# bike_sensor.net
KiCad netlist of a schematic drawn in EAGLE
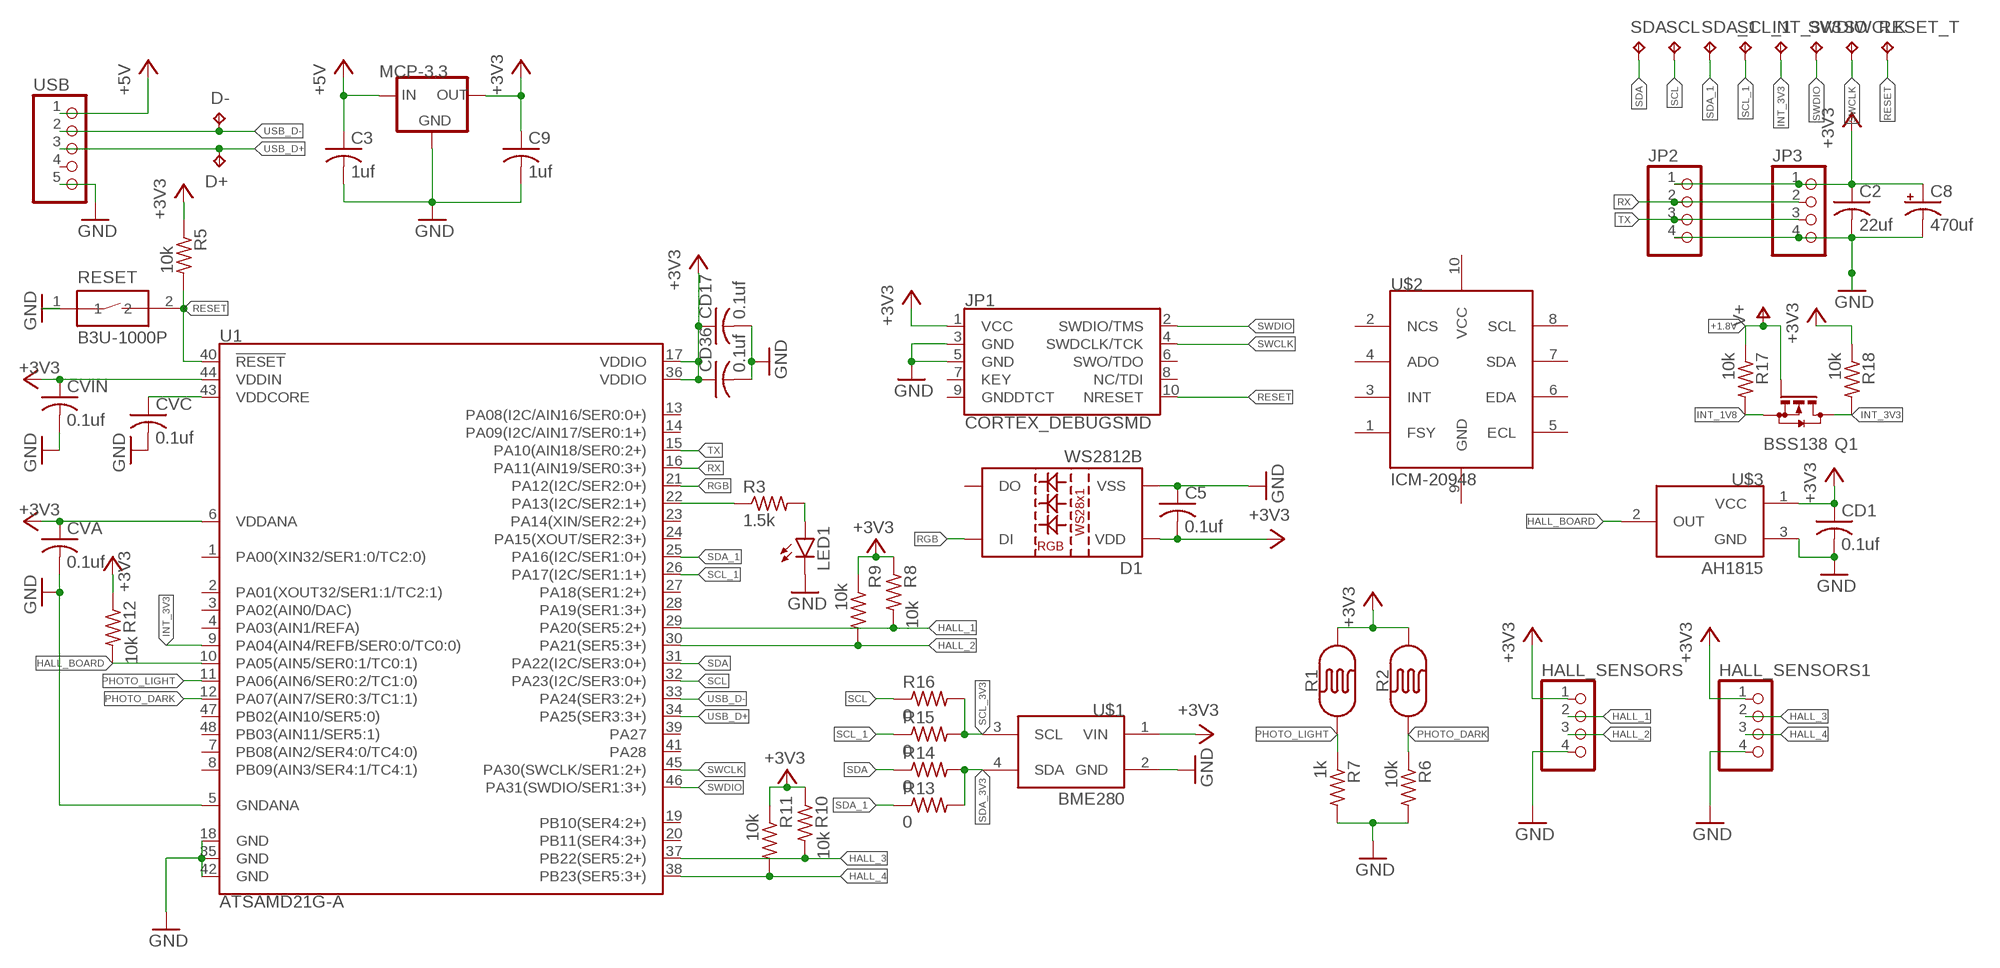
[diagram p0: schematic, sheet 1]

(export (version "E")
  (design (tool "Eeschema 10.0.6"))
  (components
    (comp (ref "C2")
      (value "22uf")
      (footprint "eagle-import:C1210")
      (libsource (lib "eagle-import") (part "C-USC1210"))
    )
    (comp (ref "C3")
      (value "1uf")
      (footprint "eagle-import:C1210")
      (libsource (lib "eagle-import") (part "C-USC1210"))
    )
    (comp (ref "C5")
      (value "0.1uf")
      (footprint "eagle-import:C0805")
      (libsource (lib "eagle-import") (part "C-USC0805"))
    )
    (comp (ref "C8")
      (value "470uf")
      (footprint "eagle-import:UD-8X10_NICHICON")
      (libsource (lib "eagle-import") (part "CPOL-USUD-8X10"))
    )
    (comp (ref "C9")
      (value "1uf")
      (footprint "eagle-import:C1210")
      (libsource (lib "eagle-import") (part "C-USC1210"))
    )
    (comp (ref "CD1")
      (value "0.1uf")
      (footprint "eagle-import:C0805")
      (libsource (lib "eagle-import") (part "C-USC0805"))
    )
    (comp (ref "CD17")
      (value "0.1uf")
      (footprint "eagle-import:C0805")
      (libsource (lib "eagle-import") (part "C-USC0805"))
    )
    (comp (ref "CD36")
      (value "0.1uf")
      (footprint "eagle-import:C0805")
      (libsource (lib "eagle-import") (part "C-USC0805"))
    )
    (comp (ref "CVA")
      (value "0.1uf")
      (footprint "eagle-import:C0805")
      (libsource (lib "eagle-import") (part "C-USC0805"))
    )
    (comp (ref "CVC")
      (value "0.1uf")
      (footprint "eagle-import:C0805")
      (libsource (lib "eagle-import") (part "C-USC0805"))
    )
    (comp (ref "CVIN")
      (value "0.1uf")
      (footprint "eagle-import:C0805")
      (libsource (lib "eagle-import") (part "C-USC0805"))
    )
    (comp (ref "D+")
      (value "TPB1,27")
      (footprint "eagle-import:B1,27")
      (libsource (lib "eagle-import") (part "TPB1,27"))
    )
    (comp (ref "D-")
      (value "TPB1,27")
      (footprint "eagle-import:B1,27")
      (libsource (lib "eagle-import") (part "TPB1,27"))
    )
    (comp (ref "D1")
      (value "WS2812B")
      (footprint "eagle-import:WS2812B")
      (libsource (lib "eagle-import") (part "WS2812B"))
    )
    (comp (ref "HALL_SENSORS")
      (value "PINHD-1X4")
      (footprint "eagle-import:1X04")
      (libsource (lib "eagle-import") (part "PINHD-1X4"))
    )
    (comp (ref "HALL_SENSORS1")
      (value "PINHD-1X4")
      (footprint "eagle-import:1X04")
      (libsource (lib "eagle-import") (part "PINHD-1X4"))
    )
    (comp (ref "INT_3V3")
      (value "TPB1,27")
      (footprint "eagle-import:B1,27")
      (libsource (lib "eagle-import") (part "TPB1,27"))
    )
    (comp (ref "JP1")
      (value "CORTEX_DEBUGSMD")
      (footprint "eagle-import:SAMTECH_FTSH-105-01")
      (libsource (lib "eagle-import") (part "CORTEX_DEBUGSMD"))
    )
    (comp (ref "JP2")
      (value "PINHD-1X4")
      (footprint "eagle-import:1X04")
      (libsource (lib "eagle-import") (part "PINHD-1X4"))
    )
    (comp (ref "JP3")
      (value "PINHD-1X4")
      (footprint "eagle-import:1X04")
      (libsource (lib "eagle-import") (part "PINHD-1X4"))
    )
    (comp (ref "LED1")
      (value "LEDCHIPLED_0805")
      (footprint "eagle-import:CHIPLED_0805")
      (libsource (lib "eagle-import") (part "LEDCHIPLED_0805"))
    )
    (comp (ref "MCP-3.3")
      (value "XC63FPM")
      (footprint "eagle-import:SOT23")
      (libsource (lib "eagle-import") (part "XC63FPM"))
    )
    (comp (ref "Q1")
      (value "BSS138")
      (footprint "eagle-import:SOT23")
      (libsource (lib "eagle-import") (part "BSS123"))
    )
    (comp (ref "R1")
      (value "PHOTOCELLPTH")
      (footprint "eagle-import:PHOTOCELL")
      (libsource (lib "eagle-import") (part "PHOTOCELLPTH"))
    )
    (comp (ref "R2")
      (value "PHOTOCELLPTH")
      (footprint "eagle-import:PHOTOCELL")
      (libsource (lib "eagle-import") (part "PHOTOCELLPTH"))
    )
    (comp (ref "R3")
      (value "1.5k")
      (footprint "eagle-import:R0805")
      (libsource (lib "eagle-import") (part "R-US_R0805"))
    )
    (comp (ref "R5")
      (value "10k")
      (footprint "eagle-import:R0805")
      (libsource (lib "eagle-import") (part "R-US_R0805"))
    )
    (comp (ref "R6")
      (value "10k")
      (footprint "eagle-import:R0805")
      (libsource (lib "eagle-import") (part "R-US_R0805"))
    )
    (comp (ref "R7")
      (value "1k")
      (footprint "eagle-import:R0805")
      (libsource (lib "eagle-import") (part "R-US_R0805"))
    )
    (comp (ref "R8")
      (value "10k")
      (footprint "eagle-import:R0805")
      (libsource (lib "eagle-import") (part "R-US_R0805"))
    )
    (comp (ref "R9")
      (value "10k")
      (footprint "eagle-import:R0805")
      (libsource (lib "eagle-import") (part "R-US_R0805"))
    )
    (comp (ref "R10")
      (value "10k")
      (footprint "eagle-import:R0805")
      (libsource (lib "eagle-import") (part "R-US_R0805"))
    )
    (comp (ref "R11")
      (value "10k")
      (footprint "eagle-import:R0805")
      (libsource (lib "eagle-import") (part "R-US_R0805"))
    )
    (comp (ref "R12")
      (value "10k")
      (footprint "eagle-import:R0805")
      (libsource (lib "eagle-import") (part "R-US_R0805"))
    )
    (comp (ref "R13")
      (value "0")
      (footprint "eagle-import:R0603")
      (libsource (lib "eagle-import") (part "R-US_R0603"))
    )
    (comp (ref "R14")
      (value "0")
      (footprint "eagle-import:R0603")
      (libsource (lib "eagle-import") (part "R-US_R0603"))
    )
    (comp (ref "R15")
      (value "0")
      (footprint "eagle-import:R0603")
      (libsource (lib "eagle-import") (part "R-US_R0603"))
    )
    (comp (ref "R16")
      (value "0")
      (footprint "eagle-import:R0603")
      (libsource (lib "eagle-import") (part "R-US_R0603"))
    )
    (comp (ref "R17")
      (value "10k")
      (footprint "eagle-import:R0805")
      (libsource (lib "eagle-import") (part "R-US_R0805"))
    )
    (comp (ref "R18")
      (value "10k")
      (footprint "eagle-import:R0805")
      (libsource (lib "eagle-import") (part "R-US_R0805"))
    )
    (comp (ref "RESET")
      (value "B3U-1000P")
      (footprint "eagle-import:B3U-1000P")
      (fields
        (field (name "DIGI_KEY_PART_NUMBER") "SW1020CT-ND")
        (field (name "MANUFACTURER") "Omron Electronics Inc-EMC Div")
        (field (name "CREATED_BY") "PCBLayout.com")
      )
      (libsource (lib "eagle-import") (part "B3U-1000P"))
    )
    (comp (ref "RESET_T")
      (value "TPB1,27")
      (footprint "eagle-import:B1,27")
      (libsource (lib "eagle-import") (part "TPB1,27"))
    )
    (comp (ref "SCL")
      (value "TPB1,27")
      (footprint "eagle-import:B1,27")
      (libsource (lib "eagle-import") (part "TPB1,27"))
    )
    (comp (ref "SCL_1")
      (value "TPB1,27")
      (footprint "eagle-import:B1,27")
      (libsource (lib "eagle-import") (part "TPB1,27"))
    )
    (comp (ref "SDA")
      (value "TPB1,27")
      (footprint "eagle-import:B1,27")
      (libsource (lib "eagle-import") (part "TPB1,27"))
    )
    (comp (ref "SDA_1")
      (value "TPB1,27")
      (footprint "eagle-import:B1,27")
      (libsource (lib "eagle-import") (part "TPB1,27"))
    )
    (comp (ref "SWCLK")
      (value "TPB1,27")
      (footprint "eagle-import:B1,27")
      (libsource (lib "eagle-import") (part "TPB1,27"))
    )
    (comp (ref "SWDIO")
      (value "TPB1,27")
      (footprint "eagle-import:B1,27")
      (libsource (lib "eagle-import") (part "TPB1,27"))
    )
    (comp (ref "U$1")
      (value "BMP280")
      (footprint "eagle-import:BME280-BOARD")
      (libsource (lib "eagle-import") (part "BMP280"))
    )
    (comp (ref "U$2")
      (value "MPU9250")
      (footprint "eagle-import:ICM-20948-BOARD")
      (libsource (lib "eagle-import") (part "MPU9250"))
    )
    (comp (ref "U$3")
      (value "AH1815")
      (footprint "eagle-import:SOT23")
      (libsource (lib "eagle-import") (part "AH1815"))
    )
    (comp (ref "U1")
      (value "ATSAMD21G-A")
      (footprint "eagle-import:TQFP-48")
      (libsource (lib "eagle-import") (part "ATSAMD21G-A"))
    )
    (comp (ref "USB")
      (value "PINHD-1X5")
      (footprint "eagle-import:1X05")
      (libsource (lib "eagle-import") (part "PINHD-1X5"))
    )
  )
  (nets
    (net (code "1") (name "+1.8V") (class "Default")
      (node (ref "Q1") (pin "1") (pinfunction "G_1") (pintype "passive"))
      (node (ref "R17") (pin "1") (pinfunction "1_1") (pintype "passive"))
    )
    (net (code "2") (name "+3V3") (class "Default")
      (node (ref "C2") (pin "1") (pinfunction "1_1") (pintype "passive"))
      (node (ref "C5") (pin "2") (pinfunction "2_2") (pintype "passive"))
      (node (ref "C8") (pin "+") (pinfunction "+_+") (pintype "passive"))
      (node (ref "C9") (pin "1") (pinfunction "1_1") (pintype "passive"))
      (node (ref "CD1") (pin "1") (pinfunction "1_1") (pintype "passive"))
      (node (ref "CD17") (pin "1") (pinfunction "1_1") (pintype "passive"))
      (node (ref "CD36") (pin "1") (pinfunction "1_1") (pintype "passive"))
      (node (ref "CVA") (pin "1") (pinfunction "1_1") (pintype "passive"))
      (node (ref "CVIN") (pin "1") (pinfunction "1_1") (pintype "passive"))
      (node (ref "D1") (pin "1") (pinfunction "VDD_1") (pintype "bidirectional"))
      (node (ref "HALL_SENSORS") (pin "1") (pinfunction "1_1") (pintype "passive"))
      (node (ref "HALL_SENSORS1") (pin "1") (pinfunction "1_1") (pintype "passive"))
      (node (ref "JP1") (pin "1") (pinfunction "VCC_1") (pintype "bidirectional"))
      (node (ref "JP2") (pin "1") (pinfunction "1_1") (pintype "passive"))
      (node (ref "JP3") (pin "1") (pinfunction "1_1") (pintype "passive"))
      (node (ref "MCP-3.3") (pin "2") (pinfunction "OUT_2") (pintype "passive"))
      (node (ref "R1") (pin "2") (pinfunction "P$2_2") (pintype "bidirectional"))
      (node (ref "R10") (pin "1") (pinfunction "1_1") (pintype "passive"))
      (node (ref "R11") (pin "1") (pinfunction "1_1") (pintype "passive"))
      (node (ref "R12") (pin "1") (pinfunction "1_1") (pintype "passive"))
      (node (ref "R18") (pin "1") (pinfunction "1_1") (pintype "passive"))
      (node (ref "R2") (pin "2") (pinfunction "P$2_2") (pintype "bidirectional"))
      (node (ref "R5") (pin "1") (pinfunction "1_1") (pintype "passive"))
      (node (ref "R8") (pin "1") (pinfunction "1_1") (pintype "passive"))
      (node (ref "R9") (pin "1") (pinfunction "1_1") (pintype "passive"))
      (node (ref "U$1") (pin "1") (pinfunction "VIN_1") (pintype "bidirectional"))
      (node (ref "U$3") (pin "1") (pinfunction "VCC_1") (pintype "power_in"))
      (node (ref "U1") (pin "17") (pinfunction "VDDIO_17") (pintype "bidirectional"))
      (node (ref "U1") (pin "36") (pinfunction "VDDIO_36") (pintype "bidirectional"))
      (node (ref "U1") (pin "44") (pinfunction "VDDIN_44") (pintype "bidirectional"))
      (node (ref "U1") (pin "6") (pinfunction "VDDANA_6") (pintype "bidirectional"))
    )
    (net (code "3") (name "+5V") (class "Default")
      (node (ref "C3") (pin "1") (pinfunction "1_1") (pintype "passive"))
      (node (ref "MCP-3.3") (pin "3") (pinfunction "IN_3") (pintype "input"))
      (node (ref "USB") (pin "1") (pinfunction "1_1") (pintype "passive"))
    )
    (net (code "4") (name "/VCC") (class "Default")
      (node (ref "U$2") (pin "10") (pinfunction "VCC_10") (pintype "power_in"))
    )
    (net (code "5") (name "GND") (class "Default")
      (node (ref "C2") (pin "2") (pinfunction "2_2") (pintype "passive"))
      (node (ref "C3") (pin "2") (pinfunction "2_2") (pintype "passive"))
      (node (ref "C5") (pin "1") (pinfunction "1_1") (pintype "passive"))
      (node (ref "C8") (pin "-") (pinfunction "-_-") (pintype "passive"))
      (node (ref "C9") (pin "2") (pinfunction "2_2") (pintype "passive"))
      (node (ref "CD1") (pin "2") (pinfunction "2_2") (pintype "passive"))
      (node (ref "CD17") (pin "2") (pinfunction "2_2") (pintype "passive"))
      (node (ref "CD36") (pin "2") (pinfunction "2_2") (pintype "passive"))
      (node (ref "CVA") (pin "2") (pinfunction "2_2") (pintype "passive"))
      (node (ref "CVC") (pin "2") (pinfunction "2_2") (pintype "passive"))
      (node (ref "CVIN") (pin "2") (pinfunction "2_2") (pintype "passive"))
      (node (ref "D1") (pin "3") (pinfunction "VSS_3") (pintype "bidirectional"))
      (node (ref "HALL_SENSORS") (pin "4") (pinfunction "4_4") (pintype "passive"))
      (node (ref "HALL_SENSORS1") (pin "4") (pinfunction "4_4") (pintype "passive"))
      (node (ref "JP1") (pin "3") (pinfunction "GND_3") (pintype "bidirectional"))
      (node (ref "JP1") (pin "5") (pinfunction "GND_5") (pintype "bidirectional"))
      (node (ref "JP2") (pin "4") (pinfunction "4_4") (pintype "passive"))
      (node (ref "JP3") (pin "4") (pinfunction "4_4") (pintype "passive"))
      (node (ref "LED1") (pin "C") (pinfunction "C_C") (pintype "passive"))
      (node (ref "MCP-3.3") (pin "1") (pinfunction "GND_1") (pintype "input"))
      (node (ref "R6") (pin "2") (pinfunction "2_2") (pintype "passive"))
      (node (ref "R7") (pin "2") (pinfunction "2_2") (pintype "passive"))
      (node (ref "RESET") (pin "1") (pinfunction "1_1") (pintype "passive"))
      (node (ref "U$1") (pin "2") (pinfunction "GND_2") (pintype "bidirectional"))
      (node (ref "U$3") (pin "3") (pinfunction "GND_3") (pintype "power_in"))
      (node (ref "U1") (pin "18") (pinfunction "GND_18") (pintype "bidirectional"))
      (node (ref "U1") (pin "35") (pinfunction "GND_35") (pintype "bidirectional"))
      (node (ref "U1") (pin "42") (pinfunction "GND_42") (pintype "bidirectional"))
      (node (ref "U1") (pin "5") (pinfunction "GNDANA_5") (pintype "bidirectional"))
      (node (ref "USB") (pin "5") (pinfunction "5_5") (pintype "passive"))
    )
    (net (code "6") (name "HALL_1") (class "Default")
      (node (ref "HALL_SENSORS") (pin "2") (pinfunction "2_2") (pintype "passive"))
      (node (ref "R8") (pin "2") (pinfunction "2_2") (pintype "passive"))
      (node (ref "U1") (pin "29") (pinfunction "PA20(SER5:2+)_29") (pintype "bidirectional"))
    )
    (net (code "7") (name "HALL_2") (class "Default")
      (node (ref "HALL_SENSORS") (pin "3") (pinfunction "3_3") (pintype "passive"))
      (node (ref "R9") (pin "2") (pinfunction "2_2") (pintype "passive"))
      (node (ref "U1") (pin "30") (pinfunction "PA21(SER5:3+)_30") (pintype "bidirectional"))
    )
    (net (code "8") (name "HALL_3") (class "Default")
      (node (ref "HALL_SENSORS1") (pin "2") (pinfunction "2_2") (pintype "passive"))
      (node (ref "R10") (pin "2") (pinfunction "2_2") (pintype "passive"))
      (node (ref "U1") (pin "37") (pinfunction "PB22(SER5:2+)_37") (pintype "bidirectional"))
    )
    (net (code "9") (name "HALL_4") (class "Default")
      (node (ref "HALL_SENSORS1") (pin "3") (pinfunction "3_3") (pintype "passive"))
      (node (ref "R11") (pin "2") (pinfunction "2_2") (pintype "passive"))
      (node (ref "U1") (pin "38") (pinfunction "PB23(SER5:3+)_38") (pintype "bidirectional"))
    )
    (net (code "10") (name "HALL_BOARD") (class "Default")
      (node (ref "R12") (pin "2") (pinfunction "2_2") (pintype "passive"))
      (node (ref "U$3") (pin "2") (pinfunction "OUT_2") (pintype "output"))
      (node (ref "U1") (pin "10") (pinfunction "PA05(AIN5/SER0:1/TC0:1)_10") (pintype "bidirectional"))
    )
    (net (code "11") (name "INT_1V8") (class "Default")
      (node (ref "Q1") (pin "2") (pinfunction "S_2") (pintype "passive"))
      (node (ref "R17") (pin "2") (pinfunction "2_2") (pintype "passive"))
    )
    (net (code "12") (name "INT_3V3") (class "Default")
      (node (ref "INT_3V3") (pin "TP") (pinfunction "TP_TP") (pintype "input"))
      (node (ref "Q1") (pin "3") (pinfunction "D_3") (pintype "passive"))
      (node (ref "R18") (pin "2") (pinfunction "2_2") (pintype "passive"))
      (node (ref "U1") (pin "9") (pinfunction "PA04(AIN4/REFB/SER0:0/TC0:0)_9") (pintype "bidirectional"))
    )
    (net (code "13") (name "Net-(LED1-PadA)") (class "Default")
      (node (ref "LED1") (pin "A") (pinfunction "A_A") (pintype "passive"))
      (node (ref "R3") (pin "2") (pinfunction "2_2") (pintype "passive"))
    )
    (net (code "14") (name "Net-(U1-PA13(I2C{slash}SER2:1+))") (class "Default")
      (node (ref "R3") (pin "1") (pinfunction "1_1") (pintype "passive"))
      (node (ref "U1") (pin "22") (pinfunction "PA13(I2C/SER2:1+)_22") (pintype "bidirectional"))
    )
    (net (code "15") (name "Net-(U1-VDDCORE)") (class "Default")
      (node (ref "CVC") (pin "1") (pinfunction "1_1") (pintype "passive"))
      (node (ref "U1") (pin "43") (pinfunction "VDDCORE_43") (pintype "bidirectional"))
    )
    (net (code "16") (name "PHOTO_DARK") (class "Default")
      (node (ref "R2") (pin "1") (pinfunction "P$1_1") (pintype "bidirectional"))
      (node (ref "R6") (pin "1") (pinfunction "1_1") (pintype "passive"))
      (node (ref "U1") (pin "12") (pinfunction "PA07(AIN7/SER0:3/TC1:1)_12") (pintype "bidirectional"))
    )
    (net (code "17") (name "PHOTO_LIGHT") (class "Default")
      (node (ref "R1") (pin "1") (pinfunction "P$1_1") (pintype "bidirectional"))
      (node (ref "R7") (pin "1") (pinfunction "1_1") (pintype "passive"))
      (node (ref "U1") (pin "11") (pinfunction "PA06(AIN6/SER0:2/TC1:0)_11") (pintype "bidirectional"))
    )
    (net (code "18") (name "RESET") (class "Default")
      (node (ref "JP1") (pin "10") (pinfunction "NRESET_10") (pintype "bidirectional"))
      (node (ref "R5") (pin "2") (pinfunction "2_2") (pintype "passive"))
      (node (ref "RESET") (pin "2") (pinfunction "2_2") (pintype "passive"))
      (node (ref "RESET_T") (pin "TP") (pinfunction "TP_TP") (pintype "input"))
      (node (ref "U1") (pin "40") (pinfunction "~{RESET}_40") (pintype "bidirectional"))
    )
    (net (code "19") (name "RGB") (class "Default")
      (node (ref "D1") (pin "4") (pinfunction "DI_4") (pintype "bidirectional"))
      (node (ref "U1") (pin "21") (pinfunction "PA12(I2C/SER2:0+)_21") (pintype "bidirectional"))
    )
    (net (code "20") (name "RX") (class "Default")
      (node (ref "JP2") (pin "2") (pinfunction "2_2") (pintype "passive"))
      (node (ref "JP3") (pin "2") (pinfunction "2_2") (pintype "passive"))
      (node (ref "U1") (pin "16") (pinfunction "PA11(AIN19/SER0:3+)_16") (pintype "bidirectional"))
    )
    (net (code "21") (name "SCL") (class "Default")
      (node (ref "R16") (pin "1") (pinfunction "1_1") (pintype "passive"))
      (node (ref "SCL") (pin "TP") (pinfunction "TP_TP") (pintype "input"))
      (node (ref "U1") (pin "32") (pinfunction "PA23(I2C/SER3:0+)_32") (pintype "bidirectional"))
    )
    (net (code "22") (name "SCL_1") (class "Default")
      (node (ref "R15") (pin "1") (pinfunction "1_1") (pintype "passive"))
      (node (ref "SCL_1") (pin "TP") (pinfunction "TP_TP") (pintype "input"))
      (node (ref "U1") (pin "26") (pinfunction "PA17(I2C/SER1:1+)_26") (pintype "bidirectional"))
    )
    (net (code "23") (name "SCL_3V3") (class "Default")
      (node (ref "R15") (pin "2") (pinfunction "2_2") (pintype "passive"))
      (node (ref "R16") (pin "2") (pinfunction "2_2") (pintype "passive"))
      (node (ref "U$1") (pin "3") (pinfunction "SCL_3") (pintype "bidirectional"))
    )
    (net (code "24") (name "SDA") (class "Default")
      (node (ref "R14") (pin "1") (pinfunction "1_1") (pintype "passive"))
      (node (ref "SDA") (pin "TP") (pinfunction "TP_TP") (pintype "input"))
      (node (ref "U1") (pin "31") (pinfunction "PA22(I2C/SER3:0+)_31") (pintype "bidirectional"))
    )
    (net (code "25") (name "SDA_1") (class "Default")
      (node (ref "R13") (pin "1") (pinfunction "1_1") (pintype "passive"))
      (node (ref "SDA_1") (pin "TP") (pinfunction "TP_TP") (pintype "input"))
      (node (ref "U1") (pin "25") (pinfunction "PA16(I2C/SER1:0+)_25") (pintype "bidirectional"))
    )
    (net (code "26") (name "SDA_3V3") (class "Default")
      (node (ref "R13") (pin "2") (pinfunction "2_2") (pintype "passive"))
      (node (ref "R14") (pin "2") (pinfunction "2_2") (pintype "passive"))
      (node (ref "U$1") (pin "4") (pinfunction "SDA_4") (pintype "bidirectional"))
    )
    (net (code "27") (name "SWCLK") (class "Default")
      (node (ref "JP1") (pin "4") (pinfunction "SWDCLK/TCK_4") (pintype "bidirectional"))
      (node (ref "SWCLK") (pin "TP") (pinfunction "TP_TP") (pintype "input"))
      (node (ref "U1") (pin "45") (pinfunction "PA30(SWCLK/SER1:2+)_45") (pintype "bidirectional"))
    )
    (net (code "28") (name "SWDIO") (class "Default")
      (node (ref "JP1") (pin "2") (pinfunction "SWDIO/TMS_2") (pintype "bidirectional"))
      (node (ref "SWDIO") (pin "TP") (pinfunction "TP_TP") (pintype "input"))
      (node (ref "U1") (pin "46") (pinfunction "PA31(SWDIO/SER1:3+)_46") (pintype "bidirectional"))
    )
    (net (code "29") (name "TX") (class "Default")
      (node (ref "JP2") (pin "3") (pinfunction "3_3") (pintype "passive"))
      (node (ref "JP3") (pin "3") (pinfunction "3_3") (pintype "passive"))
      (node (ref "U1") (pin "15") (pinfunction "PA10(AIN18/SER0:2+)_15") (pintype "bidirectional"))
    )
    (net (code "30") (name "USB_D+") (class "Default")
      (node (ref "D+") (pin "TP") (pinfunction "TP_TP") (pintype "input"))
      (node (ref "U1") (pin "34") (pinfunction "PA25(SER3:3+)_34") (pintype "bidirectional"))
      (node (ref "USB") (pin "3") (pinfunction "3_3") (pintype "passive"))
    )
    (net (code "31") (name "USB_D-") (class "Default")
      (node (ref "D-") (pin "TP") (pinfunction "TP_TP") (pintype "input"))
      (node (ref "U1") (pin "33") (pinfunction "PA24(SER3:2+)_33") (pintype "bidirectional"))
      (node (ref "USB") (pin "2") (pinfunction "2_2") (pintype "passive"))
    )
    (net (code "32") (name "unconnected-(D1-DO-Pad2)") (class "Default")
      (node (ref "D1") (pin "2") (pinfunction "DO_2") (pintype "bidirectional"))
    )
    (net (code "33") (name "unconnected-(JP1-GNDDTCT-Pad9)") (class "Default")
      (node (ref "JP1") (pin "9") (pinfunction "GNDDTCT_9") (pintype "bidirectional"))
    )
    (net (code "34") (name "unconnected-(JP1-KEY-Pad7)") (class "Default")
      (node (ref "JP1") (pin "7") (pinfunction "KEY_7") (pintype "bidirectional"))
    )
    (net (code "35") (name "unconnected-(JP1-NC{slash}TDI-Pad8)") (class "Default")
      (node (ref "JP1") (pin "8") (pinfunction "NC/TDI_8") (pintype "bidirectional"))
    )
    (net (code "36") (name "unconnected-(JP1-SWO{slash}TDO-Pad6)") (class "Default")
      (node (ref "JP1") (pin "6") (pinfunction "SWO/TDO_6") (pintype "bidirectional"))
    )
    (net (code "37") (name "unconnected-(U$2-ADO-Pad4)") (class "Default")
      (node (ref "U$2") (pin "4") (pinfunction "ADO_4") (pintype "bidirectional"))
    )
    (net (code "38") (name "unconnected-(U$2-ECL-Pad5)") (class "Default")
      (node (ref "U$2") (pin "5") (pinfunction "ECL_5") (pintype "bidirectional"))
    )
    (net (code "39") (name "unconnected-(U$2-EDA-Pad6)") (class "Default")
      (node (ref "U$2") (pin "6") (pinfunction "EDA_6") (pintype "bidirectional"))
    )
    (net (code "40") (name "unconnected-(U$2-FSY-Pad1)") (class "Default")
      (node (ref "U$2") (pin "1") (pinfunction "FSY_1") (pintype "bidirectional"))
    )
    (net (code "41") (name "unconnected-(U$2-GND-Pad9)") (class "Default")
      (node (ref "U$2") (pin "9") (pinfunction "GND_9") (pintype "bidirectional"))
    )
    (net (code "42") (name "unconnected-(U$2-INT-Pad3)") (class "Default")
      (node (ref "U$2") (pin "3") (pinfunction "INT_3") (pintype "bidirectional"))
    )
    (net (code "43") (name "unconnected-(U$2-NCS-Pad2)") (class "Default")
      (node (ref "U$2") (pin "2") (pinfunction "NCS_2") (pintype "bidirectional"))
    )
    (net (code "44") (name "unconnected-(U$2-SCL-Pad8)") (class "Default")
      (node (ref "U$2") (pin "8") (pinfunction "SCL_8") (pintype "bidirectional"))
    )
    (net (code "45") (name "unconnected-(U$2-SDA-Pad7)") (class "Default")
      (node (ref "U$2") (pin "7") (pinfunction "SDA_7") (pintype "bidirectional"))
    )
    (net (code "46") (name "unconnected-(U1-PA00(XIN32{slash}SER1:0{slash}TC2:0)-Pad1)") (class "Default")
      (node (ref "U1") (pin "1") (pinfunction "PA00(XIN32/SER1:0/TC2:0)_1") (pintype "bidirectional"))
    )
    (net (code "47") (name "unconnected-(U1-PA01(XOUT32{slash}SER1:1{slash}TC2:1)-Pad2)") (class "Default")
      (node (ref "U1") (pin "2") (pinfunction "PA01(XOUT32/SER1:1/TC2:1)_2") (pintype "bidirectional"))
    )
    (net (code "48") (name "unconnected-(U1-PA02(AIN0{slash}DAC)-Pad3)") (class "Default")
      (node (ref "U1") (pin "3") (pinfunction "PA02(AIN0/DAC)_3") (pintype "bidirectional"))
    )
    (net (code "49") (name "unconnected-(U1-PA03(AIN1{slash}REFA)-Pad4)") (class "Default")
      (node (ref "U1") (pin "4") (pinfunction "PA03(AIN1/REFA)_4") (pintype "bidirectional"))
    )
    (net (code "50") (name "unconnected-(U1-PA08(I2C{slash}AIN16{slash}SER0:0+)-Pad13)") (class "Default")
      (node (ref "U1") (pin "13") (pinfunction "PA08(I2C/AIN16/SER0:0+)_13") (pintype "bidirectional"))
    )
    (net (code "51") (name "unconnected-(U1-PA09(I2C{slash}AIN17{slash}SER0:1+)-Pad14)") (class "Default")
      (node (ref "U1") (pin "14") (pinfunction "PA09(I2C/AIN17/SER0:1+)_14") (pintype "bidirectional"))
    )
    (net (code "52") (name "unconnected-(U1-PA14(XIN{slash}SER2:2+)-Pad23)") (class "Default")
      (node (ref "U1") (pin "23") (pinfunction "PA14(XIN/SER2:2+)_23") (pintype "bidirectional"))
    )
    (net (code "53") (name "unconnected-(U1-PA15(XOUT{slash}SER2:3+)-Pad24)") (class "Default")
      (node (ref "U1") (pin "24") (pinfunction "PA15(XOUT/SER2:3+)_24") (pintype "bidirectional"))
    )
    (net (code "54") (name "unconnected-(U1-PA18(SER1:2+)-Pad27)") (class "Default")
      (node (ref "U1") (pin "27") (pinfunction "PA18(SER1:2+)_27") (pintype "bidirectional"))
    )
    (net (code "55") (name "unconnected-(U1-PA19(SER1:3+)-Pad28)") (class "Default")
      (node (ref "U1") (pin "28") (pinfunction "PA19(SER1:3+)_28") (pintype "bidirectional"))
    )
    (net (code "56") (name "unconnected-(U1-PA27-Pad39)") (class "Default")
      (node (ref "U1") (pin "39") (pinfunction "PA27_39") (pintype "bidirectional"))
    )
    (net (code "57") (name "unconnected-(U1-PA28-Pad41)") (class "Default")
      (node (ref "U1") (pin "41") (pinfunction "PA28_41") (pintype "bidirectional"))
    )
    (net (code "58") (name "unconnected-(U1-PB02(AIN10{slash}SER5:0)-Pad47)") (class "Default")
      (node (ref "U1") (pin "47") (pinfunction "PB02(AIN10/SER5:0)_47") (pintype "bidirectional"))
    )
    (net (code "59") (name "unconnected-(U1-PB03(AIN11{slash}SER5:1)-Pad48)") (class "Default")
      (node (ref "U1") (pin "48") (pinfunction "PB03(AIN11/SER5:1)_48") (pintype "bidirectional"))
    )
    (net (code "60") (name "unconnected-(U1-PB08(AIN2{slash}SER4:0{slash}TC4:0)-Pad7)") (class "Default")
      (node (ref "U1") (pin "7") (pinfunction "PB08(AIN2/SER4:0/TC4:0)_7") (pintype "bidirectional"))
    )
    (net (code "61") (name "unconnected-(U1-PB09(AIN3{slash}SER4:1{slash}TC4:1)-Pad8)") (class "Default")
      (node (ref "U1") (pin "8") (pinfunction "PB09(AIN3/SER4:1/TC4:1)_8") (pintype "bidirectional"))
    )
    (net (code "62") (name "unconnected-(U1-PB10(SER4:2+)-Pad19)") (class "Default")
      (node (ref "U1") (pin "19") (pinfunction "PB10(SER4:2+)_19") (pintype "bidirectional"))
    )
    (net (code "63") (name "unconnected-(U1-PB11(SER4:3+)-Pad20)") (class "Default")
      (node (ref "U1") (pin "20") (pinfunction "PB11(SER4:3+)_20") (pintype "bidirectional"))
    )
    (net (code "64") (name "unconnected-(USB-Pad4)") (class "Default")
      (node (ref "USB") (pin "4") (pinfunction "4_4") (pintype "passive"))
    )
  )
)
